# APC_n.net
KiCad netlist of a schematic drawn in EAGLE
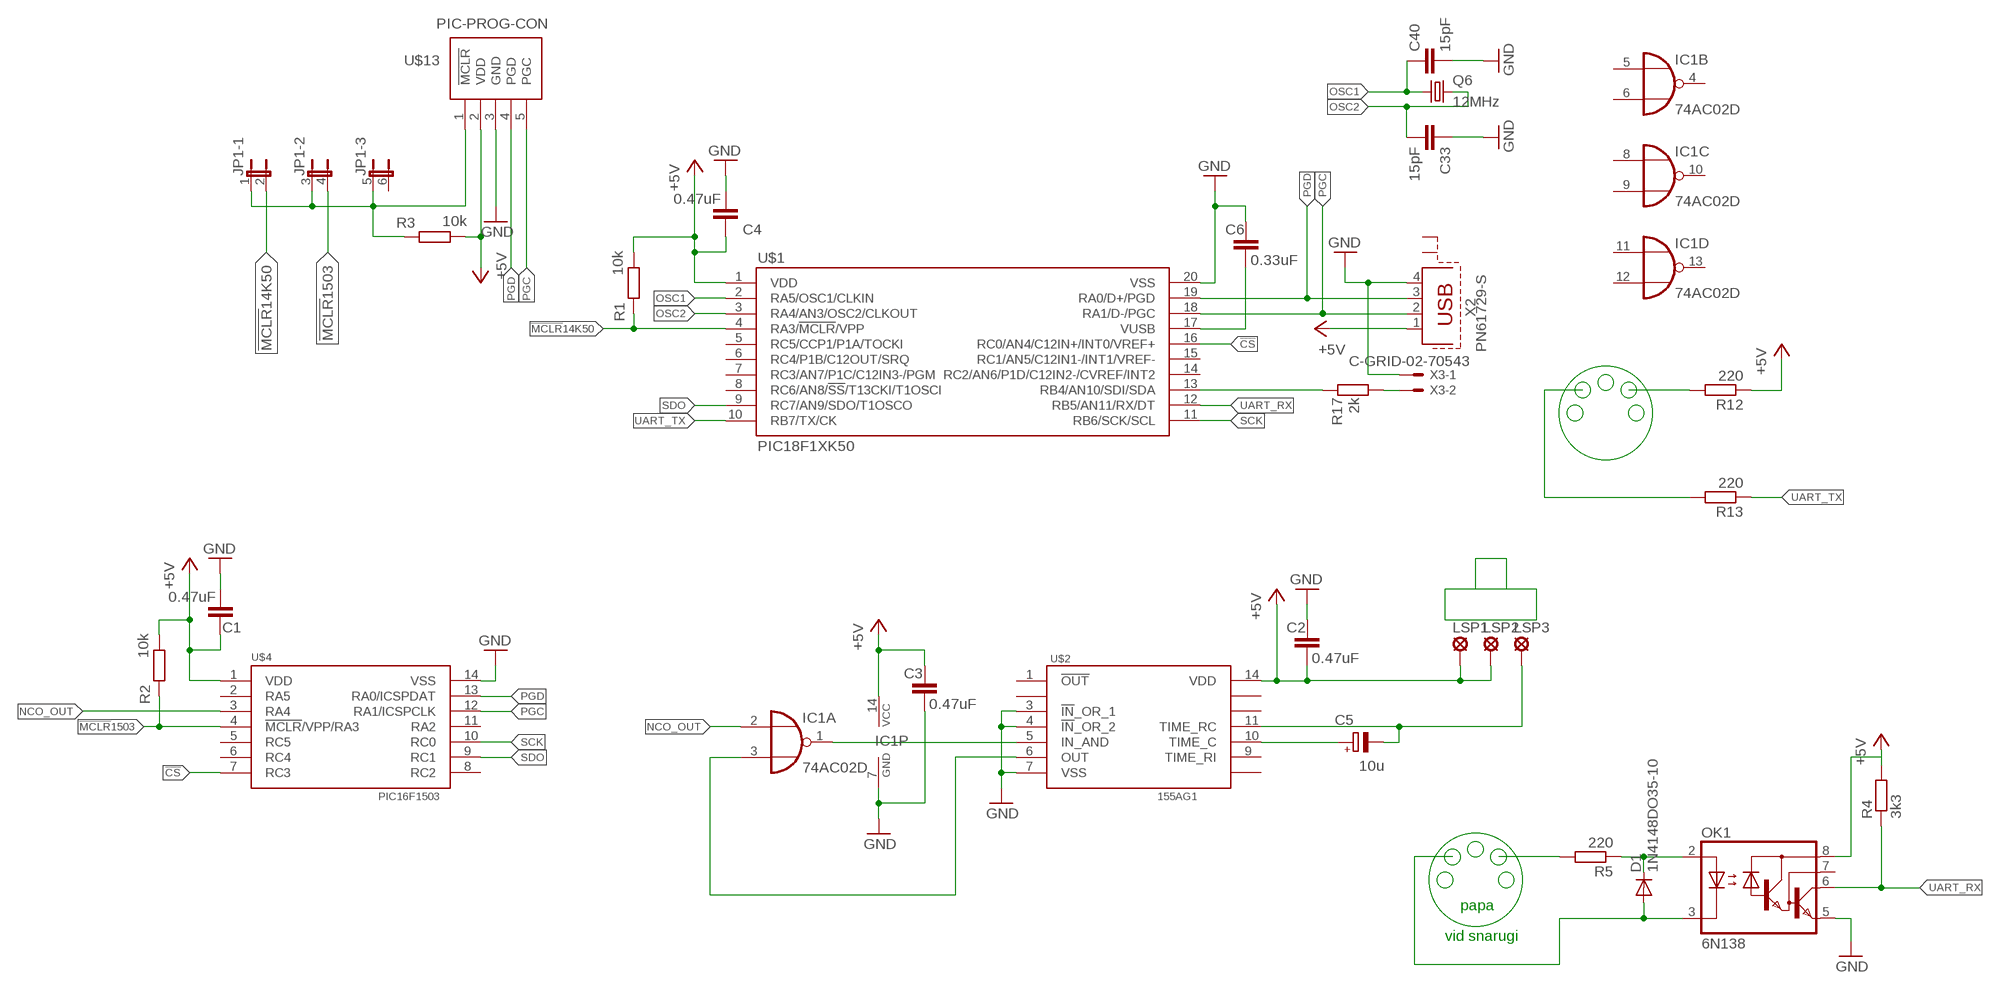
[diagram p0: schematic, sheet 1]

(export (version "E")
  (design (tool "Eeschema 10.0.6"))
  (components
    (comp (ref "C1")
      (value "0.47uF")
      (footprint "eagle-import:C1206")
      (libsource (lib "eagle-import") (part "C-1206"))
    )
    (comp (ref "C2")
      (value "0.47uF")
      (footprint "eagle-import:C1206")
      (libsource (lib "eagle-import") (part "C-1206"))
    )
    (comp (ref "C3")
      (value "0.47uF")
      (footprint "eagle-import:C1206")
      (libsource (lib "eagle-import") (part "C-1206"))
    )
    (comp (ref "C4")
      (value "0.47uF")
      (footprint "eagle-import:C1206")
      (libsource (lib "eagle-import") (part "C-1206"))
    )
    (comp (ref "C5")
      (value "10u")
      (footprint "eagle-import:CT3528")
      (libsource (lib "eagle-import") (part "CPOL-EUCT3528"))
    )
    (comp (ref "C6")
      (value "0.33uF")
      (footprint "eagle-import:C1206")
      (libsource (lib "eagle-import") (part "C-1206"))
    )
    (comp (ref "C33")
      (value "15pF")
      (footprint "eagle-import:C1206")
      (libsource (lib "eagle-import") (part "C-1206"))
    )
    (comp (ref "C40")
      (value "15pF")
      (footprint "eagle-import:C1206")
      (libsource (lib "eagle-import") (part "C-1206"))
    )
    (comp (ref "D1")
      (value "1N4148DO35-10")
      (footprint "eagle-import:DO35-10")
      (libsource (lib "eagle-import") (part "1N4148DO35-10"))
    )
    (comp (ref "IC1")
      (value "74AC02D")
      (footprint "eagle-import:SO14")
      (libsource (lib "eagle-import") (part "7402DAC"))
    )
    (comp (ref "JP1")
      (value "JP3QE")
      (footprint "eagle-import:JP3Q")
      (libsource (lib "eagle-import") (part "JP3QE"))
    )
    (comp (ref "LSP1")
      (value "SE13")
      (footprint "eagle-import:SE13")
      (libsource (lib "eagle-import") (part "SE13"))
    )
    (comp (ref "LSP2")
      (value "SE13")
      (footprint "eagle-import:SE13")
      (libsource (lib "eagle-import") (part "SE13"))
    )
    (comp (ref "LSP3")
      (value "SE13")
      (footprint "eagle-import:SE13")
      (libsource (lib "eagle-import") (part "SE13"))
    )
    (comp (ref "OK1")
      (value "6N138")
      (footprint "eagle-import:DIL08")
      (libsource (lib "eagle-import") (part "6N138"))
    )
    (comp (ref "Q6")
      (value "12MHz")
      (footprint "eagle-import:HC49_S")
      (libsource (lib "eagle-import") (part "CRYSTALHC49S"))
    )
    (comp (ref "R1")
      (value "10k")
      (footprint "eagle-import:M1206")
      (libsource (lib "eagle-import") (part "R-EU_M1206"))
    )
    (comp (ref "R2")
      (value "10k")
      (footprint "eagle-import:M1206")
      (libsource (lib "eagle-import") (part "R-EU_M1206"))
    )
    (comp (ref "R3")
      (value "10k")
      (footprint "eagle-import:M1206")
      (libsource (lib "eagle-import") (part "R-EU_M1206"))
    )
    (comp (ref "R4")
      (value "3k3")
      (footprint "eagle-import:M1206")
      (libsource (lib "eagle-import") (part "R-EU_M1206"))
    )
    (comp (ref "R5")
      (value "220")
      (footprint "eagle-import:M1206")
      (libsource (lib "eagle-import") (part "R-EU_M1206"))
    )
    (comp (ref "R12")
      (value "220")
      (footprint "eagle-import:M1206")
      (libsource (lib "eagle-import") (part "R-EU_M1206"))
    )
    (comp (ref "R13")
      (value "220")
      (footprint "eagle-import:M1206")
      (libsource (lib "eagle-import") (part "R-EU_M1206"))
    )
    (comp (ref "R17")
      (value "2k")
      (footprint "eagle-import:M1206")
      (libsource (lib "eagle-import") (part "R-EU_M1206"))
    )
    (comp (ref "U$1")
      (value "PIC18F1XK50")
      (footprint "eagle-import:SOIC20")
      (libsource (lib "eagle-import") (part "PIC18F1XK50"))
    )
    (comp (ref "U$2")
      (value "155AG1")
      (footprint "eagle-import:DIP14")
      (libsource (lib "eagle-import") (part "155AG1"))
    )
    (comp (ref "U$4")
      (value "PIC16F1503")
      (footprint "eagle-import:SO14")
      (libsource (lib "eagle-import") (part "PIC16F1503"))
    )
    (comp (ref "U$13")
      (value "PIC-PROG-CON")
      (footprint "eagle-import:PIC-PROG-CON")
      (libsource (lib "eagle-import") (part "PIC-PROG-CON"))
    )
    (comp (ref "X2")
      (value "PN61729-S")
      (footprint "eagle-import:PN61729-S")
      (libsource (lib "eagle-import") (part "PN61729-S"))
    )
    (comp (ref "X3")
      (value "C-GRID-02-70543")
      (footprint "eagle-import:70543-02")
      (libsource (lib "eagle-import") (part "C-GRID-02-70543"))
    )
  )
  (nets
    (net (code "1") (name "+5V") (class "Default")
      (node (ref "C1") (pin "2") (pinfunction "2_2") (pintype "passive"))
      (node (ref "C2") (pin "1") (pinfunction "1_1") (pintype "passive"))
      (node (ref "C3") (pin "2") (pinfunction "2_2") (pintype "passive"))
      (node (ref "C4") (pin "2") (pinfunction "2_2") (pintype "passive"))
      (node (ref "IC1") (pin "14") (pinfunction "VCC_14") (pintype "power_in"))
      (node (ref "LSP1") (pin "MP") (pinfunction "MP_MP") (pintype "passive"))
      (node (ref "LSP2") (pin "MP") (pinfunction "MP_MP") (pintype "passive"))
      (node (ref "OK1") (pin "8") (pinfunction "VCC_8") (pintype "passive"))
      (node (ref "R1") (pin "2") (pinfunction "2_2") (pintype "passive"))
      (node (ref "R12") (pin "1") (pinfunction "1_1") (pintype "passive"))
      (node (ref "R2") (pin "2") (pinfunction "2_2") (pintype "passive"))
      (node (ref "R3") (pin "2") (pinfunction "2_2") (pintype "passive"))
      (node (ref "R4") (pin "2") (pinfunction "2_2") (pintype "passive"))
      (node (ref "U$1") (pin "1") (pinfunction "VDD_1") (pintype "bidirectional"))
      (node (ref "U$13") (pin "2") (pinfunction "VDD_2") (pintype "bidirectional"))
      (node (ref "U$2") (pin "14") (pinfunction "VDD_14") (pintype "bidirectional"))
      (node (ref "U$4") (pin "1") (pinfunction "VDD_1") (pintype "bidirectional"))
      (node (ref "X2") (pin "1") (pinfunction "1_1") (pintype "passive"))
    )
    (net (code "2") (name "/~{CS}") (class "Default")
      (node (ref "U$1") (pin "16") (pinfunction "RC0/AN4/C12IN+/INT0/VREF+_16") (pintype "bidirectional"))
      (node (ref "U$4") (pin "7") (pinfunction "RC3_7") (pintype "bidirectional"))
    )
    (net (code "3") (name "/~{MCLR}14K50") (class "Default")
      (node (ref "JP1") (pin "2") (pinfunction "2_2") (pintype "passive"))
      (node (ref "R1") (pin "1") (pinfunction "1_1") (pintype "passive"))
      (node (ref "U$1") (pin "4") (pinfunction "RA3/~{MCLR}/VPP_4") (pintype "bidirectional"))
    )
    (net (code "4") (name "/~{MCLR}1503") (class "Default")
      (node (ref "JP1") (pin "4") (pinfunction "2_4") (pintype "passive"))
      (node (ref "R2") (pin "1") (pinfunction "1_1") (pintype "passive"))
      (node (ref "U$4") (pin "4") (pinfunction "~{MCLR}/VPP/RA3_4") (pintype "bidirectional"))
    )
    (net (code "5") (name "GND") (class "Default")
      (node (ref "C1") (pin "1") (pinfunction "1_1") (pintype "passive"))
      (node (ref "C2") (pin "2") (pinfunction "2_2") (pintype "passive"))
      (node (ref "C3") (pin "1") (pinfunction "1_1") (pintype "passive"))
      (node (ref "C33") (pin "1") (pinfunction "1_1") (pintype "passive"))
      (node (ref "C4") (pin "1") (pinfunction "1_1") (pintype "passive"))
      (node (ref "C40") (pin "2") (pinfunction "2_2") (pintype "passive"))
      (node (ref "C6") (pin "2") (pinfunction "2_2") (pintype "passive"))
      (node (ref "IC1") (pin "7") (pinfunction "GND_7") (pintype "power_in"))
      (node (ref "OK1") (pin "5") (pinfunction "GND_5") (pintype "passive"))
      (node (ref "U$1") (pin "20") (pinfunction "VSS_20") (pintype "bidirectional"))
      (node (ref "U$13") (pin "3") (pinfunction "GND_3") (pintype "bidirectional"))
      (node (ref "U$2") (pin "3") (pinfunction "~{IN}_OR_1_3") (pintype "bidirectional"))
      (node (ref "U$2") (pin "4") (pinfunction "~{IN}_OR_2_4") (pintype "bidirectional"))
      (node (ref "U$2") (pin "7") (pinfunction "VSS_7") (pintype "bidirectional"))
      (node (ref "U$4") (pin "14") (pinfunction "VSS_14") (pintype "bidirectional"))
      (node (ref "X2") (pin "4") (pinfunction "4_4") (pintype "passive"))
      (node (ref "X3") (pin "1") (pinfunction "S_1") (pintype "passive"))
    )
    (net (code "6") (name "NCO_OUT") (class "Default")
      (node (ref "IC1") (pin "2") (pinfunction "I0_2") (pintype "input"))
      (node (ref "U$4") (pin "3") (pinfunction "RA4_3") (pintype "bidirectional"))
    )
    (net (code "7") (name "Net-(IC1A-I1)") (class "Default")
      (node (ref "IC1") (pin "3") (pinfunction "I1_3") (pintype "input"))
      (node (ref "U$2") (pin "6") (pinfunction "OUT_6") (pintype "bidirectional"))
    )
    (net (code "8") (name "Net-(IC1A-O)") (class "Default")
      (node (ref "IC1") (pin "1") (pinfunction "O_1") (pintype "output"))
      (node (ref "U$2") (pin "5") (pinfunction "IN_AND_5") (pintype "bidirectional"))
    )
    (net (code "9") (name "Net-(JP1B-1)") (class "Default")
      (node (ref "JP1") (pin "1") (pinfunction "1_1") (pintype "passive"))
      (node (ref "JP1") (pin "3") (pinfunction "1_3") (pintype "passive"))
      (node (ref "JP1") (pin "5") (pinfunction "1_5") (pintype "passive"))
      (node (ref "R3") (pin "1") (pinfunction "1_1") (pintype "passive"))
      (node (ref "U$13") (pin "1") (pinfunction "~{MCLR}_1") (pintype "bidirectional"))
    )
    (net (code "10") (name "Net-(OK1-A)") (class "Default")
      (node (ref "D1") (pin "C") (pinfunction "C_C") (pintype "passive"))
      (node (ref "OK1") (pin "2") (pinfunction "A_2") (pintype "passive"))
      (node (ref "R5") (pin "1") (pinfunction "1_1") (pintype "passive"))
    )
    (net (code "11") (name "Net-(OK1-C)") (class "Default")
      (node (ref "D1") (pin "A") (pinfunction "A_A") (pintype "passive"))
      (node (ref "OK1") (pin "3") (pinfunction "C_3") (pintype "passive"))
    )
    (net (code "12") (name "Net-(U$1-RB4{slash}AN10{slash}SDI{slash}SDA)") (class "Default")
      (node (ref "R17") (pin "2") (pinfunction "2_2") (pintype "passive"))
      (node (ref "U$1") (pin "13") (pinfunction "RB4/AN10/SDI/SDA_13") (pintype "bidirectional"))
    )
    (net (code "13") (name "Net-(U$1-VUSB)") (class "Default")
      (node (ref "C6") (pin "1") (pinfunction "1_1") (pintype "passive"))
      (node (ref "U$1") (pin "17") (pinfunction "VUSB_17") (pintype "bidirectional"))
    )
    (net (code "14") (name "Net-(U$2-TIME_C)") (class "Default")
      (node (ref "C5") (pin "+") (pinfunction "+_+") (pintype "passive"))
      (node (ref "U$2") (pin "10") (pinfunction "TIME_C_10") (pintype "bidirectional"))
    )
    (net (code "15") (name "Net-(U$2-TIME_RC)") (class "Default")
      (node (ref "C5") (pin "-") (pinfunction "-_-") (pintype "passive"))
      (node (ref "LSP3") (pin "MP") (pinfunction "MP_MP") (pintype "passive"))
      (node (ref "U$2") (pin "11") (pinfunction "TIME_RC_11") (pintype "bidirectional"))
    )
    (net (code "16") (name "Net-(X3B-S)") (class "Default")
      (node (ref "R17") (pin "1") (pinfunction "1_1") (pintype "passive"))
      (node (ref "X3") (pin "2") (pinfunction "S_2") (pintype "passive"))
    )
    (net (code "17") (name "OSC1") (class "Default")
      (node (ref "C40") (pin "1") (pinfunction "1_1") (pintype "passive"))
      (node (ref "Q6") (pin "1") (pinfunction "1_1") (pintype "passive"))
      (node (ref "U$1") (pin "2") (pinfunction "RA5/OSC1/CLKIN_2") (pintype "bidirectional"))
    )
    (net (code "18") (name "OSC2") (class "Default")
      (node (ref "C33") (pin "2") (pinfunction "2_2") (pintype "passive"))
      (node (ref "Q6") (pin "2") (pinfunction "2_2") (pintype "passive"))
      (node (ref "U$1") (pin "3") (pinfunction "RA4/AN3/OSC2/CLKOUT_3") (pintype "bidirectional"))
    )
    (net (code "19") (name "PGC") (class "Default")
      (node (ref "U$1") (pin "18") (pinfunction "RA1/D-/PGC_18") (pintype "bidirectional"))
      (node (ref "U$13") (pin "5") (pinfunction "PGC_5") (pintype "bidirectional"))
      (node (ref "U$4") (pin "12") (pinfunction "RA1/ICSPCLK_12") (pintype "bidirectional"))
      (node (ref "X2") (pin "2") (pinfunction "2_2") (pintype "passive"))
    )
    (net (code "20") (name "PGD") (class "Default")
      (node (ref "U$1") (pin "19") (pinfunction "RA0/D+/PGD_19") (pintype "bidirectional"))
      (node (ref "U$13") (pin "4") (pinfunction "PGD_4") (pintype "bidirectional"))
      (node (ref "U$4") (pin "13") (pinfunction "RA0/ICSPDAT_13") (pintype "bidirectional"))
      (node (ref "X2") (pin "3") (pinfunction "3_3") (pintype "passive"))
    )
    (net (code "21") (name "SCK") (class "Default")
      (node (ref "U$1") (pin "11") (pinfunction "RB6/SCK/SCL_11") (pintype "bidirectional"))
      (node (ref "U$4") (pin "10") (pinfunction "RC0_10") (pintype "bidirectional"))
    )
    (net (code "22") (name "SDO") (class "Default")
      (node (ref "U$1") (pin "9") (pinfunction "RC7/AN9/SDO/T1OSCO_9") (pintype "bidirectional"))
      (node (ref "U$4") (pin "9") (pinfunction "RC1_9") (pintype "bidirectional"))
    )
    (net (code "23") (name "UART_RX") (class "Default")
      (node (ref "OK1") (pin "6") (pinfunction "VO_6") (pintype "passive"))
      (node (ref "R4") (pin "1") (pinfunction "1_1") (pintype "passive"))
      (node (ref "U$1") (pin "12") (pinfunction "RB5/AN11/RX/DT_12") (pintype "bidirectional"))
    )
    (net (code "24") (name "UART_TX") (class "Default")
      (node (ref "R13") (pin "1") (pinfunction "1_1") (pintype "passive"))
      (node (ref "U$1") (pin "10") (pinfunction "RB7/TX/CK_10") (pintype "bidirectional"))
    )
    (net (code "25") (name "unconnected-(IC1B-I0-Pad5)") (class "Default")
      (node (ref "IC1") (pin "5") (pinfunction "I0_5") (pintype "input"))
    )
    (net (code "26") (name "unconnected-(IC1B-I1-Pad6)") (class "Default")
      (node (ref "IC1") (pin "6") (pinfunction "I1_6") (pintype "input"))
    )
    (net (code "27") (name "unconnected-(IC1B-O-Pad4)") (class "Default")
      (node (ref "IC1") (pin "4") (pinfunction "O_4") (pintype "output"))
    )
    (net (code "28") (name "unconnected-(IC1C-I0-Pad8)") (class "Default")
      (node (ref "IC1") (pin "8") (pinfunction "I0_8") (pintype "input"))
    )
    (net (code "29") (name "unconnected-(IC1C-I1-Pad9)") (class "Default")
      (node (ref "IC1") (pin "9") (pinfunction "I1_9") (pintype "input"))
    )
    (net (code "30") (name "unconnected-(IC1C-O-Pad10)") (class "Default")
      (node (ref "IC1") (pin "10") (pinfunction "O_10") (pintype "output"))
    )
    (net (code "31") (name "unconnected-(IC1D-I0-Pad11)") (class "Default")
      (node (ref "IC1") (pin "11") (pinfunction "I0_11") (pintype "input"))
    )
    (net (code "32") (name "unconnected-(IC1D-I1-Pad12)") (class "Default")
      (node (ref "IC1") (pin "12") (pinfunction "I1_12") (pintype "input"))
    )
    (net (code "33") (name "unconnected-(IC1D-O-Pad13)") (class "Default")
      (node (ref "IC1") (pin "13") (pinfunction "O_13") (pintype "output"))
    )
    (net (code "34") (name "unconnected-(JP1C-2-Pad6)") (class "Default")
      (node (ref "JP1") (pin "6") (pinfunction "2_6") (pintype "passive"))
    )
    (net (code "35") (name "unconnected-(OK1-VB-Pad7)") (class "Default")
      (node (ref "OK1") (pin "7") (pinfunction "VB_7") (pintype "passive"))
    )
    (net (code "36") (name "unconnected-(R5-Pad2)") (class "Default")
      (node (ref "R5") (pin "2") (pinfunction "2_2") (pintype "passive"))
    )
    (net (code "37") (name "unconnected-(R12-Pad2)") (class "Default")
      (node (ref "R12") (pin "2") (pinfunction "2_2") (pintype "passive"))
    )
    (net (code "38") (name "unconnected-(R13-Pad2)") (class "Default")
      (node (ref "R13") (pin "2") (pinfunction "2_2") (pintype "passive"))
    )
    (net (code "39") (name "unconnected-(U$1-RC1{slash}AN5{slash}C12IN1-{slash}INT1{slash}VREF--Pad15)") (class "Default")
      (node (ref "U$1") (pin "15") (pinfunction "RC1/AN5/C12IN1-/INT1/VREF-_15") (pintype "bidirectional"))
    )
    (net (code "40") (name "unconnected-(U$1-RC2{slash}AN6{slash}P1D{slash}C12IN2-{slash}CVREF{slash}INT2-Pad14)") (class "Default")
      (node (ref "U$1") (pin "14") (pinfunction "RC2/AN6/P1D/C12IN2-/CVREF/INT2_14") (pintype "bidirectional"))
    )
    (net (code "41") (name "unconnected-(U$1-RC3{slash}AN7{slash}P1C{slash}C12IN3-{slash}PGM-Pad7)") (class "Default")
      (node (ref "U$1") (pin "7") (pinfunction "RC3/AN7/P1C/C12IN3-/PGM_7") (pintype "bidirectional"))
    )
    (net (code "42") (name "unconnected-(U$1-RC4{slash}P1B{slash}C12OUT{slash}SRQ-Pad6)") (class "Default")
      (node (ref "U$1") (pin "6") (pinfunction "RC4/P1B/C12OUT/SRQ_6") (pintype "bidirectional"))
    )
    (net (code "43") (name "unconnected-(U$1-RC5{slash}CCP1{slash}P1A{slash}TOCKI-Pad5)") (class "Default")
      (node (ref "U$1") (pin "5") (pinfunction "RC5/CCP1/P1A/TOCKI_5") (pintype "bidirectional"))
    )
    (net (code "44") (name "unconnected-(U$1-RC6{slash}AN8{slash}~{SS}{slash}T13CKI{slash}T1OSCI-Pad8)") (class "Default")
      (node (ref "U$1") (pin "8") (pinfunction "RC6/AN8/~{SS}/T13CKI/T1OSCI_8") (pintype "bidirectional"))
    )
    (net (code "45") (name "unconnected-(U$2-NC-Pad2)") (class "Default")
      (node (ref "U$2") (pin "2") (pinfunction "NC_2") (pintype "no_connect"))
    )
    (net (code "46") (name "unconnected-(U$2-NC-Pad8)") (class "Default")
      (node (ref "U$2") (pin "8") (pinfunction "NC_8") (pintype "no_connect"))
    )
    (net (code "47") (name "unconnected-(U$2-NC-Pad12)") (class "Default")
      (node (ref "U$2") (pin "12") (pinfunction "NC_12") (pintype "no_connect"))
    )
    (net (code "48") (name "unconnected-(U$2-NC-Pad13)") (class "Default")
      (node (ref "U$2") (pin "13") (pinfunction "NC_13") (pintype "no_connect"))
    )
    (net (code "49") (name "unconnected-(U$2-TIME_RI-Pad9)") (class "Default")
      (node (ref "U$2") (pin "9") (pinfunction "TIME_RI_9") (pintype "bidirectional"))
    )
    (net (code "50") (name "unconnected-(U$2-~{OUT}-Pad1)") (class "Default")
      (node (ref "U$2") (pin "1") (pinfunction "~{OUT}_1") (pintype "bidirectional"))
    )
    (net (code "51") (name "unconnected-(U$4-RA2-Pad11)") (class "Default")
      (node (ref "U$4") (pin "11") (pinfunction "RA2_11") (pintype "bidirectional"))
    )
    (net (code "52") (name "unconnected-(U$4-RA5-Pad2)") (class "Default")
      (node (ref "U$4") (pin "2") (pinfunction "RA5_2") (pintype "bidirectional"))
    )
    (net (code "53") (name "unconnected-(U$4-RC2-Pad8)") (class "Default")
      (node (ref "U$4") (pin "8") (pinfunction "RC2_8") (pintype "bidirectional"))
    )
    (net (code "54") (name "unconnected-(U$4-RC4-Pad6)") (class "Default")
      (node (ref "U$4") (pin "6") (pinfunction "RC4_6") (pintype "bidirectional"))
    )
    (net (code "55") (name "unconnected-(U$4-RC5-Pad5)") (class "Default")
      (node (ref "U$4") (pin "5") (pinfunction "RC5_5") (pintype "bidirectional"))
    )
    (net (code "56") (name "unconnected-(X2-PadS1)") (class "Default")
      (node (ref "X2") (pin "S1") (pinfunction "S1_S1") (pintype "passive"))
    )
    (net (code "57") (name "unconnected-(X2-PadS2)") (class "Default")
      (node (ref "X2") (pin "S2") (pinfunction "S2_S2") (pintype "passive"))
    )
  )
)
